# Pyr0-Piezo_Direct_Extruder_Board2_0_1.net
KiCad netlist of a schematic drawn in EAGLE
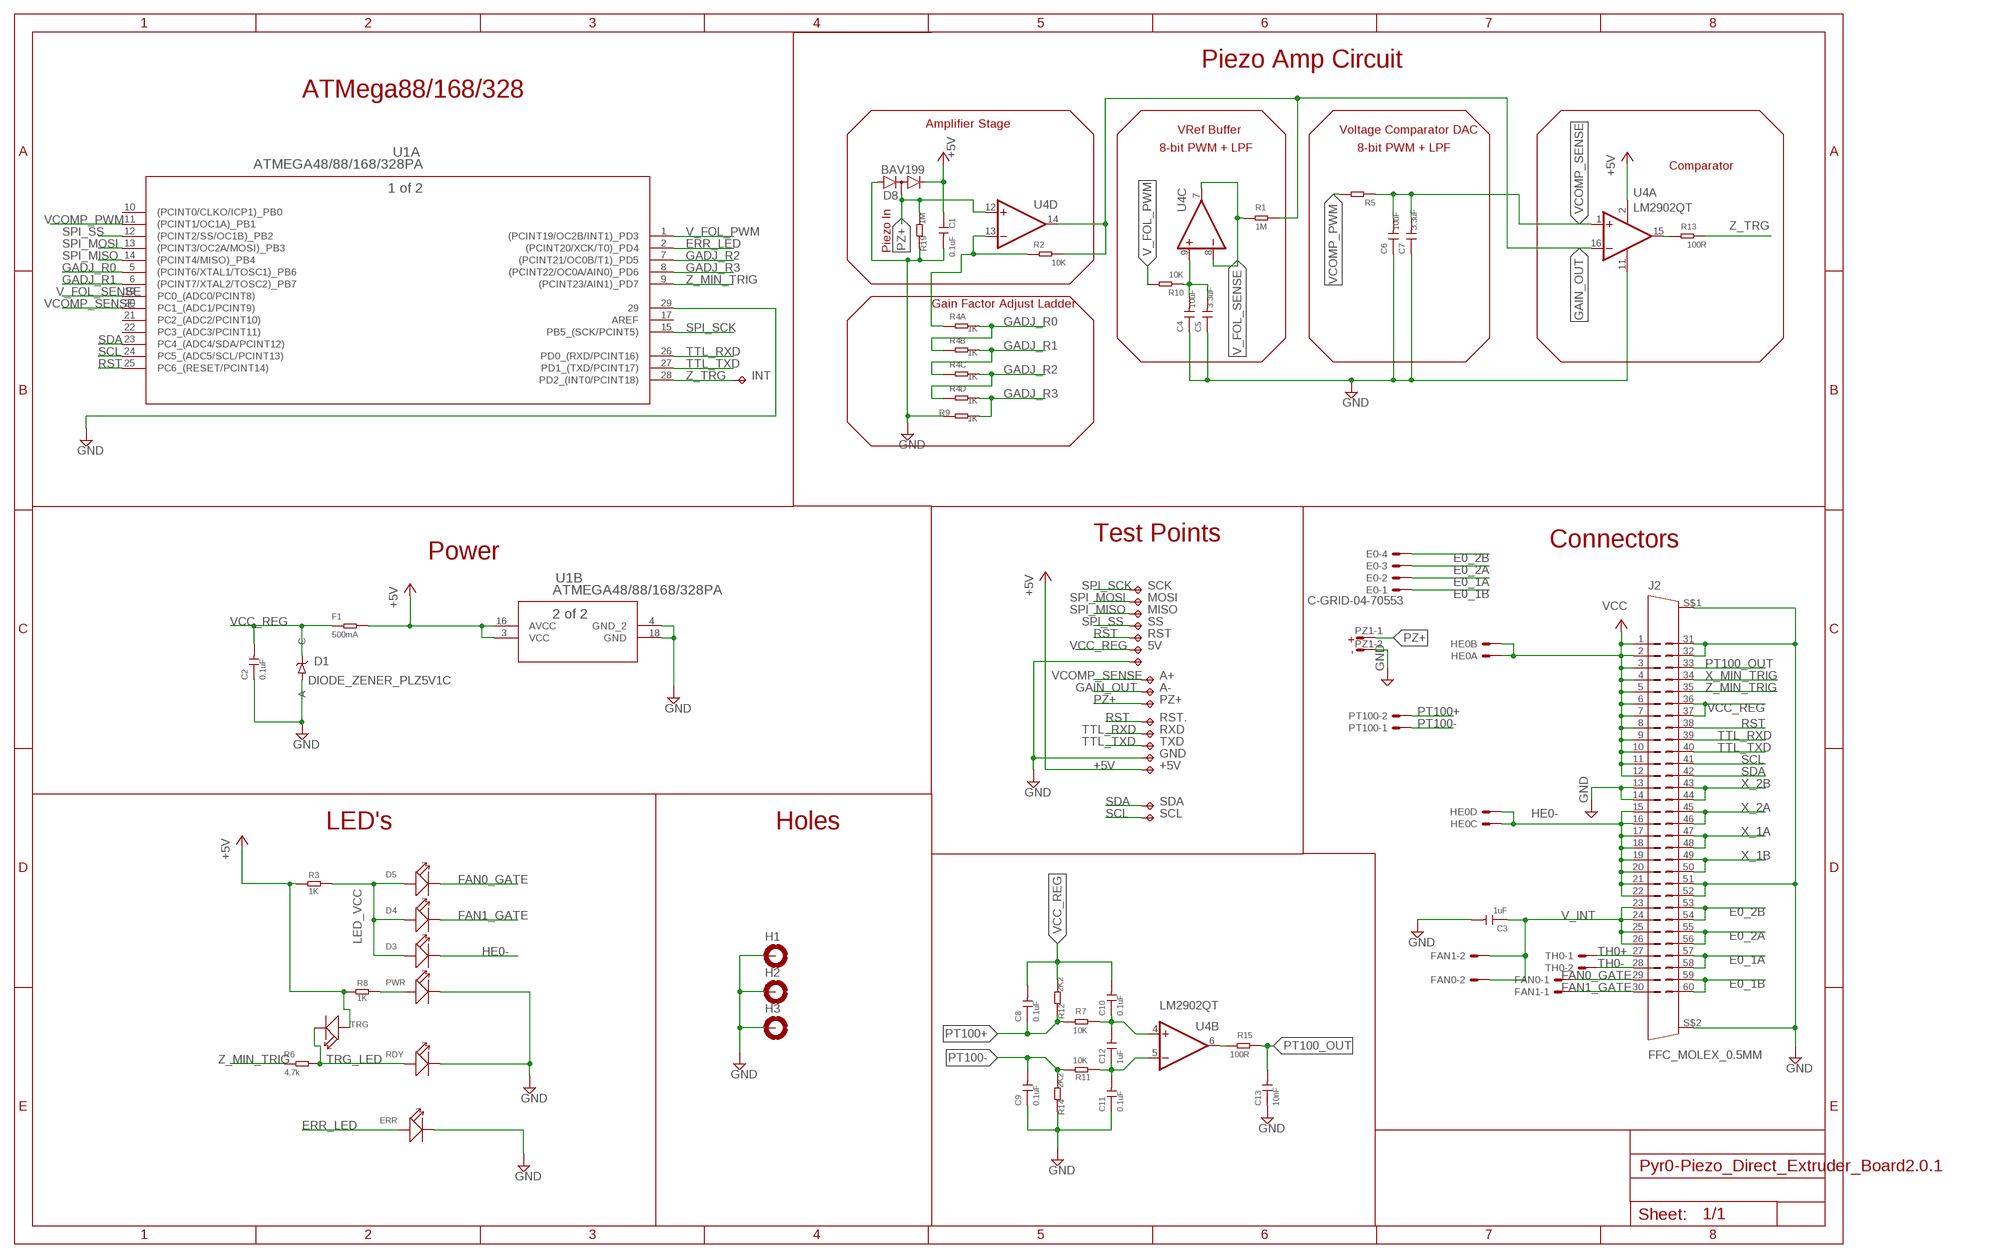
[diagram p0: schematic, sheet 1]

(export (version "E")
  (design (tool "Eeschema 10.0.6"))
  (components
    (comp (ref "+5V")
      (value "TPTP13SQ")
      (footprint "eagle-import:TP13SQ")
      (libsource (lib "eagle-import") (part "testpad_385_TPTP13SQ"))
    )
    (comp (ref "5V")
      (value "TPTP13SQ")
      (footprint "eagle-import:TP13SQ")
      (libsource (lib "eagle-import") (part "TPTP13SQ"))
    )
    (comp (ref "A+")
      (value "TPTP13SQ")
      (footprint "eagle-import:TP13SQ")
      (libsource (lib "eagle-import") (part "TPTP13SQ"))
    )
    (comp (ref "A-")
      (value "TPTP13SQ")
      (footprint "eagle-import:TP13SQ")
      (libsource (lib "eagle-import") (part "TPTP13SQ"))
    )
    (comp (ref "C1")
      (value "0.1uF")
      (footprint "eagle-import:CAPC1005X50")
      (libsource (lib "eagle-import") (part "CERAMIC-1NF-50V-10%-X7R(0402)CAP_0402"))
    )
    (comp (ref "C2")
      (value "0.1uF")
      (footprint "eagle-import:CAPC1005X50")
      (libsource (lib "eagle-import") (part "CERAMIC-1NF-50V-10%-X7R(0402)CAP_0402"))
    )
    (comp (ref "C3")
      (value "1uF")
      (footprint "eagle-import:CAPC1609X80")
      (libsource (lib "eagle-import") (part "SEEED-CAPACITOR_CERAMIC-10UF-25V-10%-X5R(0805)CAP_0603_GEN"))
    )
    (comp (ref "C4")
      (value "10uF")
      (footprint "eagle-import:CAPC1005X50")
      (libsource (lib "eagle-import") (part "CERAMIC-1NF-50V-10%-X7R(0402)CAP_0402"))
    )
    (comp (ref "C5")
      (value "3.3uF")
      (footprint "eagle-import:CAPC1609X80")
      (libsource (lib "eagle-import") (part "SEEED-CAPACITOR_CERAMIC-10UF-25V-10%-X5R(0805)CAP_0603_GEN"))
    )
    (comp (ref "C6")
      (value "10uF")
      (footprint "eagle-import:CAPC1005X50")
      (libsource (lib "eagle-import") (part "CERAMIC-1NF-50V-10%-X7R(0402)CAP_0402"))
    )
    (comp (ref "C7")
      (value "3.3uF")
      (footprint "eagle-import:CAPC1609X80")
      (libsource (lib "eagle-import") (part "SEEED-CAPACITOR_CERAMIC-10UF-25V-10%-X5R(0805)CAP_0603_GEN"))
    )
    (comp (ref "C8")
      (value "0.1uF")
      (footprint "eagle-import:CAPC1005X50")
      (libsource (lib "eagle-import") (part "CERAMIC-1NF-50V-10%-X7R(0402)CAP_0402"))
    )
    (comp (ref "C9")
      (value "0.1uF")
      (footprint "eagle-import:CAPC1005X50")
      (libsource (lib "eagle-import") (part "CERAMIC-1NF-50V-10%-X7R(0402)CAP_0402"))
    )
    (comp (ref "C10")
      (value "0.1uF")
      (footprint "eagle-import:CAPC1005X50")
      (libsource (lib "eagle-import") (part "CERAMIC-1NF-50V-10%-X7R(0402)CAP_0402"))
    )
    (comp (ref "C11")
      (value "0.1uF")
      (footprint "eagle-import:CAPC1005X50")
      (libsource (lib "eagle-import") (part "CERAMIC-1NF-50V-10%-X7R(0402)CAP_0402"))
    )
    (comp (ref "C12")
      (value "1uF")
      (footprint "eagle-import:CAPC1005X50")
      (libsource (lib "eagle-import") (part "CERAMIC-1NF-50V-10%-X7R(0402)CAP_0402"))
    )
    (comp (ref "C13")
      (value "10nF")
      (footprint "eagle-import:CAPC1005X50")
      (libsource (lib "eagle-import") (part "CERAMIC-1NF-50V-10%-X7R(0402)CAP_0402"))
    )
    (comp (ref "D1")
      (value "DIODE_ZENER_PLZ5V1C")
      (footprint "eagle-import:DO-219AC")
      (libsource (lib "eagle-import") (part "DIODE_ZENER_PLZ5V1C"))
    )
    (comp (ref "D3")
      (value "SEEED-LED_SMD-LED-CLEAR-BLUE(0603)LED_0603")
      (footprint "eagle-import:SEEED-LED_LED-0603")
      (libsource (lib "eagle-import") (part "SEEED-LED_SMD-LED-CLEAR-BLUE(0603)LED_0603"))
    )
    (comp (ref "D4")
      (value "SEEED-LED_SMD-LED-CLEAR-BLUE(0603)LED_0603")
      (footprint "eagle-import:SEEED-LED_LED-0603")
      (libsource (lib "eagle-import") (part "SEEED-LED_SMD-LED-CLEAR-BLUE(0603)LED_0603"))
    )
    (comp (ref "D5")
      (value "SEEED-LED_SMD-LED-CLEAR-BLUE(0603)LED_0603")
      (footprint "eagle-import:SEEED-LED_LED-0603")
      (libsource (lib "eagle-import") (part "SEEED-LED_SMD-LED-CLEAR-BLUE(0603)LED_0603"))
    )
    (comp (ref "D8")
      (value "BAV199")
      (footprint "eagle-import:SOT23")
      (libsource (lib "eagle-import") (part "BAV199"))
    )
    (comp (ref "E0")
      (value "C-GRID-04-70553")
      (footprint "eagle-import:70553-04")
      (fields (field (name "MF") "MOLEX"))
      (libsource (lib "eagle-import") (part "C-GRID-04-70553"))
    )
    (comp (ref "ERR")
      (value "SEEED-LED_SMD-LED-CLEAR-BLUE(0603)LED_0603")
      (footprint "eagle-import:SEEED-LED_LED-0603")
      (libsource (lib "eagle-import") (part "SEEED-LED_SMD-LED-CLEAR-BLUE(0603)LED_0603"))
    )
    (comp (ref "F1")
      (value "500mA")
      (footprint "eagle-import:SEEED-RESISTOR_R0603")
      (libsource (lib "eagle-import") (part "SEEED-RESISTOR_SMD-RES-1.5K-1%-1/10W(0603)DETAILED_MODEL"))
    )
    (comp (ref "FAN0")
      (value "CON-MOLEX-2P-1.27MM048")
      (footprint "eagle-import:53048-02")
      (fields (field (name "MF") "MOLEX") (field (name "MPN") "53048-0210"))
      (libsource (lib "eagle-import") (part "CON-MOLEX-2P-1.27MM048"))
    )
    (comp (ref "FAN1")
      (value "CON-MOLEX-2P-1.27MM048")
      (footprint "eagle-import:53048-02")
      (fields (field (name "MF") "MOLEX") (field (name "MPN") "53048-0210"))
      (libsource (lib "eagle-import") (part "CON-MOLEX-2P-1.27MM048"))
    )
    (comp (ref "GND")
      (value "TPTP13SQ")
      (footprint "eagle-import:TP13SQ")
      (libsource (lib "eagle-import") (part "testpad_385_TPTP13SQ"))
    )
    (comp (ref "H1")
      (value "HOLES_MOUNT-PAD-ROUND3.2")
      (footprint "eagle-import:HOLES_3,2-PAD")
      (libsource (lib "eagle-import") (part "HOLES_MOUNT-PAD-ROUND3.2"))
    )
    (comp (ref "H2")
      (value "HOLES_MOUNT-PAD-ROUND3.2")
      (footprint "eagle-import:HOLES_3,2-PAD")
      (libsource (lib "eagle-import") (part "HOLES_MOUNT-PAD-ROUND3.2"))
    )
    (comp (ref "H3")
      (value "HOLES_MOUNT-PAD-ROUND3.2")
      (footprint "eagle-import:HOLES_3,2-PAD")
      (libsource (lib "eagle-import") (part "HOLES_MOUNT-PAD-ROUND3.2"))
    )
    (comp (ref "HE0")
      (value "JST-2.54-2X2JST-DUPONT-2.54-2X2")
      (footprint "eagle-import:HDRRAR4W64P254_2X2_556X736X556B")
      (libsource (lib "eagle-import") (part "JST-2.54-2X2JST-DUPONT-2.54-2X2"))
    )
    (comp (ref "INT")
      (value "TPTP06R")
      (footprint "eagle-import:TP06R")
      (libsource (lib "eagle-import") (part "testpad_385_TPTP06R"))
    )
    (comp (ref "J2")
      (value "FFC_MOLEX_0.5MM")
      (footprint "eagle-import:FFC-60P_0.5_MOLEX_505110-6091")
      (libsource (lib "eagle-import") (part "FFC_MOLEX_0.5MM"))
    )
    (comp (ref "MISO")
      (value "TPTP13SQ")
      (footprint "eagle-import:TP13SQ")
      (libsource (lib "eagle-import") (part "TPTP13SQ"))
    )
    (comp (ref "MOSI")
      (value "TPTP13SQ")
      (footprint "eagle-import:TP13SQ")
      (libsource (lib "eagle-import") (part "TPTP13SQ"))
    )
    (comp (ref "PT100")
      (value "CON-MOLEX-2P-1.27MM048")
      (footprint "eagle-import:53048-02")
      (fields (field (name "MF") "MOLEX") (field (name "MPN") "53048-0210"))
      (libsource (lib "eagle-import") (part "CON-MOLEX-2P-1.27MM048"))
    )
    (comp (ref "PWR")
      (value "SEEED-LED_SMD-LED-CLEAR-BLUE(0603)LED_0603")
      (footprint "eagle-import:SEEED-LED_LED-0603")
      (libsource (lib "eagle-import") (part "SEEED-LED_SMD-LED-CLEAR-BLUE(0603)LED_0603"))
    )
    (comp (ref "PZ+")
      (value "TPTP13SQ")
      (footprint "eagle-import:TP13SQ")
      (libsource (lib "eagle-import") (part "TPTP13SQ"))
    )
    (comp (ref "PZ1")
      (value "CON-MOLEX-2P-1.27MM048")
      (footprint "eagle-import:53048-02")
      (fields (field (name "MF") "MOLEX") (field (name "MPN") "53048-0210"))
      (libsource (lib "eagle-import") (part "CON-MOLEX-2P-1.27MM048"))
    )
    (comp (ref "R1")
      (value "1M")
      (footprint "eagle-import:R0402")
      (fields (field (name "MPN") "RC0402JR-070RL"))
      (libsource (lib "eagle-import") (part "SMD-RES-0R-5%-1/16W(0402)"))
    )
    (comp (ref "R2")
      (value "10K")
      (footprint "eagle-import:R0402")
      (fields (field (name "MPN") "RC0402JR-070RL"))
      (libsource (lib "eagle-import") (part "SMD-RES-0R-5%-1/16W(0402)"))
    )
    (comp (ref "R3")
      (value "1K")
      (footprint "eagle-import:R0402")
      (fields (field (name "MPN") "RC0402JR-070RL"))
      (libsource (lib "eagle-import") (part "SMD-RES-0R-5%-1/16W(0402)"))
    )
    (comp (ref "R4")
      (value "1K")
      (footprint "eagle-import:EXBN8V")
      (libsource (lib "eagle-import") (part "RESISTOR_NETWORK_X40804"))
    )
    (comp (ref "R5")
      (value "10K")
      (footprint "eagle-import:SEEED-RESISTOR_R0603")
      (libsource (lib "eagle-import") (part "SEEED-RESISTOR_SMD-RES-1.5K-1%-1/10W(0603)DETAILED_MODEL"))
    )
    (comp (ref "R6")
      (value "4.7k")
      (footprint "eagle-import:R0402")
      (fields (field (name "MPN") "RC0402JR-070RL"))
      (libsource (lib "eagle-import") (part "SMD-RES-0R-5%-1/16W(0402)"))
    )
    (comp (ref "R7")
      (value "10K")
      (footprint "eagle-import:R0402")
      (fields (field (name "MPN") "RC0402JR-070RL"))
      (libsource (lib "eagle-import") (part "SMD-RES-0R-5%-1/16W(0402)"))
    )
    (comp (ref "R8")
      (value "1K")
      (footprint "eagle-import:R0402")
      (fields (field (name "MPN") "RC0402JR-070RL"))
      (libsource (lib "eagle-import") (part "SMD-RES-0R-5%-1/16W(0402)"))
    )
    (comp (ref "R9")
      (value "1K")
      (footprint "eagle-import:R0402")
      (fields (field (name "MPN") "RC0402JR-070RL"))
      (libsource (lib "eagle-import") (part "SMD-RES-0R-5%-1/16W(0402)"))
    )
    (comp (ref "R10")
      (value "10K")
      (footprint "eagle-import:R0402")
      (fields (field (name "MPN") "RC0402JR-070RL"))
      (libsource (lib "eagle-import") (part "SMD-RES-0R-5%-1/16W(0402)"))
    )
    (comp (ref "R11")
      (value "10K")
      (footprint "eagle-import:R0402")
      (fields (field (name "MPN") "RC0402JR-070RL"))
      (libsource (lib "eagle-import") (part "SMD-RES-0R-5%-1/16W(0402)"))
    )
    (comp (ref "R12")
      (value "2K2")
      (footprint "eagle-import:R0402")
      (fields (field (name "MPN") "RC0402JR-070RL"))
      (libsource (lib "eagle-import") (part "SMD-RES-0R-5%-1/16W(0402)"))
    )
    (comp (ref "R13")
      (value "100R")
      (footprint "eagle-import:R0402")
      (fields (field (name "MPN") "RC0402JR-070RL"))
      (libsource (lib "eagle-import") (part "SMD-RES-0R-5%-1/16W(0402)"))
    )
    (comp (ref "R14")
      (value "2K2")
      (footprint "eagle-import:R0402")
      (fields (field (name "MPN") "RC0402JR-070RL"))
      (libsource (lib "eagle-import") (part "SMD-RES-0R-5%-1/16W(0402)"))
    )
    (comp (ref "R15")
      (value "100R")
      (footprint "eagle-import:R0402")
      (fields (field (name "MPN") "RC0402JR-070RL"))
      (libsource (lib "eagle-import") (part "SMD-RES-0R-5%-1/16W(0402)"))
    )
    (comp (ref "R19")
      (value "1M")
      (footprint "eagle-import:R0402")
      (fields (field (name "MPN") "RC0402JR-070RL"))
      (libsource (lib "eagle-import") (part "SMD-RES-0R-5%-1/16W(0402)"))
    )
    (comp (ref "RDY")
      (value "SEEED-LED_SMD-LED-CLEAR-BLUE(0603)LED_0603")
      (footprint "eagle-import:SEEED-LED_LED-0603")
      (libsource (lib "eagle-import") (part "SEEED-LED_SMD-LED-CLEAR-BLUE(0603)LED_0603"))
    )
    (comp (ref "RST")
      (value "TPTP13SQ")
      (footprint "eagle-import:TP13SQ")
      (libsource (lib "eagle-import") (part "TPTP13SQ"))
    )
    (comp (ref "RST.")
      (value "TPTP13SQ")
      (footprint "eagle-import:TP13SQ")
      (libsource (lib "eagle-import") (part "testpad_385_TPTP13SQ"))
    )
    (comp (ref "RXD")
      (value "TPTP13SQ")
      (footprint "eagle-import:TP13SQ")
      (libsource (lib "eagle-import") (part "testpad_385_TPTP13SQ"))
    )
    (comp (ref "SCK")
      (value "TPTP13SQ")
      (footprint "eagle-import:TP13SQ")
      (libsource (lib "eagle-import") (part "TPTP13SQ"))
    )
    (comp (ref "SCL")
      (value "TPTP13SQ")
      (footprint "eagle-import:TP13SQ")
      (libsource (lib "eagle-import") (part "testpad_385_TPTP13SQ"))
    )
    (comp (ref "SDA")
      (value "TPTP13SQ")
      (footprint "eagle-import:TP13SQ")
      (libsource (lib "eagle-import") (part "testpad_385_TPTP13SQ"))
    )
    (comp (ref "SS")
      (value "TPTP06R")
      (footprint "eagle-import:TP06R")
      (libsource (lib "eagle-import") (part "testpad_385_TPTP06R"))
    )
    (comp (ref "TH0")
      (value "CON-MOLEX-2P-1.27MM048")
      (footprint "eagle-import:53048-02")
      (fields (field (name "MF") "MOLEX") (field (name "MPN") "53048-0210"))
      (libsource (lib "eagle-import") (part "CON-MOLEX-2P-1.27MM048"))
    )
    (comp (ref "TRG")
      (value "SEEED-LED_SMD-LED-CLEAR-BLUE(0603)LED_0603")
      (footprint "eagle-import:SEEED-LED_LED-0603")
      (libsource (lib "eagle-import") (part "SEEED-LED_SMD-LED-CLEAR-BLUE(0603)LED_0603"))
    )
    (comp (ref "TXD")
      (value "TPTP13SQ")
      (footprint "eagle-import:TP13SQ")
      (libsource (lib "eagle-import") (part "testpad_385_TPTP13SQ"))
    )
    (comp (ref "U1")
      (value "ATMEGA48/88/168/328PA")
      (footprint "eagle-import:28M1")
      (fields (field (name "MANUFACTURER_PART_NUMBER") "ATMEGA48PAMMHR"))
      (libsource (lib "eagle-import") (part "ATMEGA48/88/168/328PA"))
    )
    (comp (ref "U4")
      (value "LM2902QT")
      (footprint "eagle-import:QFN16")
      (libsource (lib "eagle-import") (part "LM2902QT"))
    )
    (comp (ref "⏚")
      (value "TPTP13SQ")
      (footprint "eagle-import:TP13SQ")
      (libsource (lib "eagle-import") (part "testpad_385_TPTP13SQ"))
    )
  )
  (nets
    (net (code "1") (name "+5V") (class "Default")
      (node (ref "+5V") (pin "TP") (pinfunction "TP_TP") (pintype "input"))
      (node (ref "C1") (pin "1") (pinfunction "1_1") (pintype "passive"))
      (node (ref "D8") (pin "2") (pinfunction "C_2") (pintype "passive"))
      (node (ref "F1") (pin "2") (pinfunction "2_2") (pintype "passive"))
      (node (ref "R3") (pin "1") (pinfunction "1_1") (pintype "passive"))
      (node (ref "R8") (pin "1") (pinfunction "1_1") (pintype "passive"))
      (node (ref "TRG") (pin "+") (pinfunction "+_+") (pintype "passive"))
      (node (ref "U1") (pin "16") (pinfunction "AVCC_16") (pintype "power_in"))
      (node (ref "U1") (pin "3") (pinfunction "VCC_3") (pintype "power_in"))
      (node (ref "U4") (pin "2") (pinfunction "V+_2") (pintype "power_in"))
    )
    (net (code "2") (name "/E0_1A") (class "Default")
      (node (ref "E0") (pin "2") (pinfunction "S_2") (pintype "passive"))
      (node (ref "J2") (pin "57") (pinfunction "63_57") (pintype "passive"))
      (node (ref "J2") (pin "58") (pinfunction "64_58") (pintype "passive"))
    )
    (net (code "3") (name "/E0_1B") (class "Default")
      (node (ref "E0") (pin "1") (pinfunction "S_1") (pintype "passive"))
      (node (ref "J2") (pin "59") (pinfunction "65_59") (pintype "passive"))
      (node (ref "J2") (pin "60") (pinfunction "66_60") (pintype "passive"))
    )
    (net (code "4") (name "/E0_2A") (class "Default")
      (node (ref "E0") (pin "3") (pinfunction "S_3") (pintype "passive"))
      (node (ref "J2") (pin "55") (pinfunction "61_55") (pintype "passive"))
      (node (ref "J2") (pin "56") (pinfunction "62_56") (pintype "passive"))
    )
    (net (code "5") (name "/E0_2B") (class "Default")
      (node (ref "E0") (pin "4") (pinfunction "S_4") (pintype "passive"))
      (node (ref "J2") (pin "53") (pinfunction "59_53") (pintype "passive"))
      (node (ref "J2") (pin "54") (pinfunction "60_54") (pintype "passive"))
    )
    (net (code "6") (name "/ERR_LED") (class "Default")
      (node (ref "ERR") (pin "+") (pinfunction "+_+") (pintype "passive"))
      (node (ref "U1") (pin "2") (pinfunction "(PCINT20/XCK/T0)_PD4_2") (pintype "bidirectional"))
    )
    (net (code "7") (name "/FAN0_GATE") (class "Default")
      (node (ref "D5") (pin "-") (pinfunction "-_-") (pintype "passive"))
      (node (ref "FAN0") (pin "1") (pinfunction "S_1") (pintype "passive"))
      (node (ref "J2") (pin "29") (pinfunction "31_29") (pintype "passive"))
    )
    (net (code "8") (name "/FAN1_GATE") (class "Default")
      (node (ref "D4") (pin "-") (pinfunction "-_-") (pintype "passive"))
      (node (ref "FAN1") (pin "1") (pinfunction "S_1") (pintype "passive"))
      (node (ref "J2") (pin "30") (pinfunction "32_30") (pintype "passive"))
    )
    (net (code "9") (name "/GADJ_R0") (class "Default")
      (node (ref "R4") (pin "2") (pinfunction "1_2") (pintype "passive"))
      (node (ref "R4") (pin "8") (pinfunction "2_8") (pintype "passive"))
      (node (ref "U1") (pin "5") (pinfunction "(PCINT6/XTAL1/TOSC1)_PB6_5") (pintype "bidirectional"))
    )
    (net (code "10") (name "/GADJ_R1") (class "Default")
      (node (ref "R4") (pin "3") (pinfunction "1_3") (pintype "passive"))
      (node (ref "R4") (pin "7") (pinfunction "2_7") (pintype "passive"))
      (node (ref "U1") (pin "6") (pinfunction "(PCINT7/XTAL2/TOSC2)_PB7_6") (pintype "bidirectional"))
    )
    (net (code "11") (name "/GADJ_R2") (class "Default")
      (node (ref "R4") (pin "4") (pinfunction "1_4") (pintype "passive"))
      (node (ref "R4") (pin "6") (pinfunction "2_6") (pintype "passive"))
      (node (ref "U1") (pin "7") (pinfunction "(PCINT21/OC0B/T1)_PD5_7") (pintype "bidirectional"))
    )
    (net (code "12") (name "/GADJ_R3") (class "Default")
      (node (ref "R4") (pin "5") (pinfunction "2_5") (pintype "passive"))
      (node (ref "R9") (pin "2") (pinfunction "2_2") (pintype "passive"))
      (node (ref "U1") (pin "8") (pinfunction "(PCINT22/OC0A/AIN0)_PD6_8") (pintype "bidirectional"))
    )
    (net (code "13") (name "/HE0-") (class "Default")
      (node (ref "D3") (pin "-") (pinfunction "-_-") (pintype "passive"))
      (node (ref "HE0") (pin "3") (pinfunction "S_3") (pintype "passive"))
      (node (ref "HE0") (pin "4") (pinfunction "S_4") (pintype "passive"))
      (node (ref "J2") (pin "15") (pinfunction "17_15") (pintype "passive"))
      (node (ref "J2") (pin "16") (pinfunction "18_16") (pintype "passive"))
      (node (ref "J2") (pin "17") (pinfunction "19_17") (pintype "passive"))
      (node (ref "J2") (pin "18") (pinfunction "20_18") (pintype "passive"))
      (node (ref "J2") (pin "19") (pinfunction "21_19") (pintype "passive"))
      (node (ref "J2") (pin "20") (pinfunction "22_20") (pintype "passive"))
      (node (ref "J2") (pin "21") (pinfunction "23_21") (pintype "passive"))
      (node (ref "J2") (pin "22") (pinfunction "24_22") (pintype "passive"))
    )
    (net (code "14") (name "/LED_VCC") (class "Default")
      (node (ref "D3") (pin "+") (pinfunction "+_+") (pintype "passive"))
      (node (ref "D4") (pin "+") (pinfunction "+_+") (pintype "passive"))
      (node (ref "D5") (pin "+") (pinfunction "+_+") (pintype "passive"))
      (node (ref "R3") (pin "2") (pinfunction "2_2") (pintype "passive"))
    )
    (net (code "15") (name "/RST") (class "Default")
      (node (ref "J2") (pin "38") (pinfunction "44_38") (pintype "passive"))
      (node (ref "RST") (pin "TP") (pinfunction "TP_TP") (pintype "input"))
      (node (ref "RST.") (pin "TP") (pinfunction "TP_TP") (pintype "input"))
      (node (ref "U1") (pin "25") (pinfunction "PC6_(RESET/PCINT14)_25") (pintype "bidirectional"))
    )
    (net (code "16") (name "/SCL") (class "Default")
      (node (ref "J2") (pin "41") (pinfunction "47_41") (pintype "passive"))
      (node (ref "SCL") (pin "TP") (pinfunction "TP_TP") (pintype "input"))
      (node (ref "U1") (pin "24") (pinfunction "PC5_(ADC5/SCL/PCINT13)_24") (pintype "bidirectional"))
    )
    (net (code "17") (name "/SDA") (class "Default")
      (node (ref "J2") (pin "42") (pinfunction "48_42") (pintype "passive"))
      (node (ref "SDA") (pin "TP") (pinfunction "TP_TP") (pintype "input"))
      (node (ref "U1") (pin "23") (pinfunction "PC4_(ADC4/SDA/PCINT12)_23") (pintype "bidirectional"))
    )
    (net (code "18") (name "/SPI_MISO") (class "Default")
      (node (ref "MISO") (pin "TP") (pinfunction "TP_TP") (pintype "input"))
      (node (ref "U1") (pin "14") (pinfunction "(PCINT4/MISO)_PB4_14") (pintype "bidirectional"))
    )
    (net (code "19") (name "/SPI_MOSI") (class "Default")
      (node (ref "MOSI") (pin "TP") (pinfunction "TP_TP") (pintype "input"))
      (node (ref "U1") (pin "13") (pinfunction "(PCINT3/OC2A/MOSI)_PB3_13") (pintype "bidirectional"))
    )
    (net (code "20") (name "/SPI_SCK") (class "Default")
      (node (ref "SCK") (pin "TP") (pinfunction "TP_TP") (pintype "input"))
      (node (ref "U1") (pin "15") (pinfunction "PB5_(SCK/PCINT5)_15") (pintype "bidirectional"))
    )
    (net (code "21") (name "/SPI_SS") (class "Default")
      (node (ref "SS") (pin "TP") (pinfunction "TP_TP") (pintype "input"))
      (node (ref "U1") (pin "12") (pinfunction "(PCINT2/SS/OC1B)_PB2_12") (pintype "bidirectional"))
    )
    (net (code "22") (name "/TH0+") (class "Default")
      (node (ref "J2") (pin "27") (pinfunction "29_27") (pintype "passive"))
      (node (ref "TH0") (pin "1") (pinfunction "S_1") (pintype "passive"))
    )
    (net (code "23") (name "/TH0-") (class "Default")
      (node (ref "J2") (pin "28") (pinfunction "30_28") (pintype "passive"))
      (node (ref "TH0") (pin "2") (pinfunction "S_2") (pintype "passive"))
    )
    (net (code "24") (name "/TRG_LED") (class "Default")
      (node (ref "R6") (pin "2") (pinfunction "2_2") (pintype "passive"))
      (node (ref "RDY") (pin "+") (pinfunction "+_+") (pintype "passive"))
      (node (ref "TRG") (pin "-") (pinfunction "-_-") (pintype "passive"))
    )
    (net (code "25") (name "/TTL_RXD") (class "Default")
      (node (ref "J2") (pin "39") (pinfunction "45_39") (pintype "passive"))
      (node (ref "RXD") (pin "TP") (pinfunction "TP_TP") (pintype "input"))
      (node (ref "U1") (pin "26") (pinfunction "PD0_(RXD/PCINT16)_26") (pintype "bidirectional"))
    )
    (net (code "26") (name "/TTL_TXD") (class "Default")
      (node (ref "J2") (pin "40") (pinfunction "46_40") (pintype "passive"))
      (node (ref "TXD") (pin "TP") (pinfunction "TP_TP") (pintype "input"))
      (node (ref "U1") (pin "27") (pinfunction "PD1_(TXD/PCINT17)_27") (pintype "bidirectional"))
    )
    (net (code "27") (name "/V_INT") (class "Default")
      (node (ref "C3") (pin "1") (pinfunction "1_1") (pintype "passive"))
      (node (ref "FAN0") (pin "2") (pinfunction "S_2") (pintype "passive"))
      (node (ref "FAN1") (pin "2") (pinfunction "S_2") (pintype "passive"))
      (node (ref "J2") (pin "23") (pinfunction "25_23") (pintype "passive"))
      (node (ref "J2") (pin "24") (pinfunction "26_24") (pintype "passive"))
      (node (ref "J2") (pin "25") (pinfunction "27_25") (pintype "passive"))
      (node (ref "J2") (pin "26") (pinfunction "28_26") (pintype "passive"))
    )
    (net (code "28") (name "/X_1A") (class "Default")
      (node (ref "J2") (pin "47") (pinfunction "53_47") (pintype "passive"))
      (node (ref "J2") (pin "48") (pinfunction "54_48") (pintype "passive"))
    )
    (net (code "29") (name "/X_1B") (class "Default")
      (node (ref "J2") (pin "49") (pinfunction "55_49") (pintype "passive"))
      (node (ref "J2") (pin "50") (pinfunction "56_50") (pintype "passive"))
    )
    (net (code "30") (name "/X_2A") (class "Default")
      (node (ref "J2") (pin "45") (pinfunction "51_45") (pintype "passive"))
      (node (ref "J2") (pin "46") (pinfunction "52_46") (pintype "passive"))
    )
    (net (code "31") (name "/X_2B") (class "Default")
      (node (ref "J2") (pin "43") (pinfunction "49_43") (pintype "passive"))
      (node (ref "J2") (pin "44") (pinfunction "50_44") (pintype "passive"))
    )
    (net (code "32") (name "/X_MIN_TRIG") (class "Default")
      (node (ref "J2") (pin "34") (pinfunction "40_34") (pintype "passive"))
    )
    (net (code "33") (name "/Z_MIN_TRIG") (class "Default")
      (node (ref "J2") (pin "35") (pinfunction "41_35") (pintype "passive"))
      (node (ref "R6") (pin "1") (pinfunction "1_1") (pintype "passive"))
      (node (ref "U1") (pin "9") (pinfunction "(PCINT23/AIN1)_PD7_9") (pintype "bidirectional"))
    )
    (net (code "34") (name "/Z_TRG") (class "Default")
      (node (ref "INT") (pin "TP") (pinfunction "TP_TP") (pintype "input"))
      (node (ref "R13") (pin "2") (pinfunction "2_2") (pintype "passive"))
      (node (ref "U1") (pin "28") (pinfunction "PD2_(INT0/PCINT18)_28") (pintype "bidirectional"))
    )
    (net (code "35") (name "GAIN_OUT") (class "Default")
      (node (ref "A-") (pin "TP") (pinfunction "TP_TP") (pintype "input"))
      (node (ref "R1") (pin "2") (pinfunction "2_2") (pintype "passive"))
      (node (ref "R2") (pin "2") (pinfunction "2_2") (pintype "passive"))
      (node (ref "U4") (pin "14") (pinfunction "OUT_14") (pintype "output"))
      (node (ref "U4") (pin "16") (pinfunction "-IN_16") (pintype "input"))
    )
    (net (code "36") (name "GND") (class "Default")
      (node (ref "C1") (pin "2") (pinfunction "2_2") (pintype "passive"))
      (node (ref "C11") (pin "1") (pinfunction "1_1") (pintype "passive"))
      (node (ref "C13") (pin "1") (pinfunction "1_1") (pintype "passive"))
      (node (ref "C2") (pin "1") (pinfunction "1_1") (pintype "passive"))
      (node (ref "C3") (pin "2") (pinfunction "2_2") (pintype "passive"))
      (node (ref "C4") (pin "1") (pinfunction "1_1") (pintype "passive"))
      (node (ref "C5") (pin "1") (pinfunction "1_1") (pintype "passive"))
      (node (ref "C6") (pin "1") (pinfunction "1_1") (pintype "passive"))
      (node (ref "C7") (pin "1") (pinfunction "1_1") (pintype "passive"))
      (node (ref "C9") (pin "1") (pinfunction "1_1") (pintype "passive"))
      (node (ref "D1") (pin "P$1") (pinfunction "A_P$1") (pintype "passive"))
      (node (ref "D8") (pin "1") (pinfunction "A_1") (pintype "passive"))
      (node (ref "ERR") (pin "-") (pinfunction "-_-") (pintype "passive"))
      (node (ref "GND") (pin "TP") (pinfunction "TP_TP") (pintype "input"))
      (node (ref "H1") (pin "B3,2") (pinfunction "MOUNT_B3,2") (pintype "passive"))
      (node (ref "H2") (pin "B3,2") (pinfunction "MOUNT_B3,2") (pintype "passive"))
      (node (ref "H3") (pin "B3,2") (pinfunction "MOUNT_B3,2") (pintype "passive"))
      (node (ref "J2") (pin "13") (pinfunction "15_13") (pintype "passive"))
      (node (ref "J2") (pin "14") (pinfunction "16_14") (pintype "passive"))
      (node (ref "J2") (pin "31") (pinfunction "37_31") (pintype "passive"))
      (node (ref "J2") (pin "32") (pinfunction "38_32") (pintype "passive"))
      (node (ref "J2") (pin "51") (pinfunction "57_51") (pintype "passive"))
      (node (ref "J2") (pin "52") (pinfunction "58_52") (pintype "passive"))
      (node (ref "J2") (pin "S$1") (pinfunction "S_S$1") (pintype "passive"))
      (node (ref "J2") (pin "S$2") (pinfunction "S_S$2") (pintype "passive"))
      (node (ref "PWR") (pin "-") (pinfunction "-_-") (pintype "passive"))
      (node (ref "PZ1") (pin "2") (pinfunction "S_2") (pintype "passive"))
      (node (ref "R14") (pin "1") (pinfunction "1_1") (pintype "passive"))
      (node (ref "R19") (pin "1") (pinfunction "1_1") (pintype "passive"))
      (node (ref "R9") (pin "1") (pinfunction "1_1") (pintype "passive"))
      (node (ref "RDY") (pin "-") (pinfunction "-_-") (pintype "passive"))
      (node (ref "U1") (pin "18") (pinfunction "GND_18") (pintype "power_in"))
      (node (ref "U1") (pin "29") (pinfunction "29_29") (pintype "passive"))
      (node (ref "U1") (pin "4") (pinfunction "GND_2_4") (pintype "power_in"))
      (node (ref "U4") (pin "11") (pinfunction "V-_11") (pintype "power_in"))
      (node (ref "⏚") (pin "TP") (pinfunction "TP_TP") (pintype "input"))
    )
    (net (code "37") (name "Net-(PWR-Pad+)") (class "Default")
      (node (ref "PWR") (pin "+") (pinfunction "+_+") (pintype "passive"))
      (node (ref "R8") (pin "2") (pinfunction "2_2") (pintype "passive"))
    )
    (net (code "38") (name "Net-(U4A-OUT)") (class "Default")
      (node (ref "R13") (pin "1") (pinfunction "1_1") (pintype "passive"))
      (node (ref "U4") (pin "15") (pinfunction "OUT_15") (pintype "output"))
    )
    (net (code "39") (name "Net-(U4B-+IN)") (class "Default")
      (node (ref "C10") (pin "1") (pinfunction "1_1") (pintype "passive"))
      (node (ref "C12") (pin "2") (pinfunction "2_2") (pintype "passive"))
      (node (ref "R7") (pin "1") (pinfunction "1_1") (pintype "passive"))
      (node (ref "U4") (pin "4") (pinfunction "+IN_4") (pintype "input"))
    )
    (net (code "40") (name "Net-(U4B--IN)") (class "Default")
      (node (ref "C11") (pin "2") (pinfunction "2_2") (pintype "passive"))
      (node (ref "C12") (pin "1") (pinfunction "1_1") (pintype "passive"))
      (node (ref "R11") (pin "1") (pinfunction "1_1") (pintype "passive"))
      (node (ref "U4") (pin "5") (pinfunction "-IN_5") (pintype "input"))
    )
    (net (code "41") (name "Net-(U4B-OUT)") (class "Default")
      (node (ref "R15") (pin "2") (pinfunction "2_2") (pintype "passive"))
      (node (ref "U4") (pin "6") (pinfunction "OUT_6") (pintype "output"))
    )
    (net (code "42") (name "Net-(U4C-+IN)") (class "Default")
      (node (ref "C4") (pin "2") (pinfunction "2_2") (pintype "passive"))
      (node (ref "C5") (pin "2") (pinfunction "2_2") (pintype "passive"))
      (node (ref "R10") (pin "1") (pinfunction "1_1") (pintype "passive"))
      (node (ref "U4") (pin "9") (pinfunction "+IN_9") (pintype "input"))
    )
    (net (code "43") (name "Net-(U4D--IN)") (class "Default")
      (node (ref "R2") (pin "1") (pinfunction "1_1") (pintype "passive"))
      (node (ref "R4") (pin "1") (pinfunction "1_1") (pintype "passive"))
      (node (ref "U4") (pin "13") (pinfunction "-IN_13") (pintype "input"))
    )
    (net (code "44") (name "PT100+") (class "Default")
      (node (ref "C8") (pin "1") (pinfunction "1_1") (pintype "passive"))
      (node (ref "PT100") (pin "2") (pinfunction "S_2") (pintype "passive"))
      (node (ref "R12") (pin "1") (pinfunction "1_1") (pintype "passive"))
      (node (ref "R7") (pin "2") (pinfunction "2_2") (pintype "passive"))
    )
    (net (code "45") (name "PT100-") (class "Default")
      (node (ref "C9") (pin "2") (pinfunction "2_2") (pintype "passive"))
      (node (ref "PT100") (pin "1") (pinfunction "S_1") (pintype "passive"))
      (node (ref "R11") (pin "2") (pinfunction "2_2") (pintype "passive"))
      (node (ref "R14") (pin "2") (pinfunction "2_2") (pintype "passive"))
    )
    (net (code "46") (name "PT100_OUT") (class "Default")
      (node (ref "C13") (pin "2") (pinfunction "2_2") (pintype "passive"))
      (node (ref "J2") (pin "33") (pinfunction "39_33") (pintype "passive"))
      (node (ref "R15") (pin "1") (pinfunction "1_1") (pintype "passive"))
    )
    (net (code "47") (name "PZ+") (class "Default")
      (node (ref "D8") (pin "3") (pinfunction "AC_3") (pintype "passive"))
      (node (ref "PZ+") (pin "TP") (pinfunction "TP_TP") (pintype "input"))
      (node (ref "PZ1") (pin "1") (pinfunction "S_1") (pintype "passive"))
      (node (ref "R19") (pin "2") (pinfunction "2_2") (pintype "passive"))
      (node (ref "U4") (pin "12") (pinfunction "+IN_12") (pintype "input"))
    )
    (net (code "48") (name "VCC") (class "Default")
      (node (ref "HE0") (pin "1") (pinfunction "S_1") (pintype "passive"))
      (node (ref "HE0") (pin "2") (pinfunction "S_2") (pintype "passive"))
      (node (ref "J2") (pin "1") (pinfunction "3_1") (pintype "passive"))
      (node (ref "J2") (pin "10") (pinfunction "12_10") (pintype "passive"))
      (node (ref "J2") (pin "11") (pinfunction "13_11") (pintype "passive"))
      (node (ref "J2") (pin "12") (pinfunction "14_12") (pintype "passive"))
      (node (ref "J2") (pin "2") (pinfunction "4_2") (pintype "passive"))
      (node (ref "J2") (pin "3") (pinfunction "5_3") (pintype "passive"))
      (node (ref "J2") (pin "4") (pinfunction "6_4") (pintype "passive"))
      (node (ref "J2") (pin "5") (pinfunction "7_5") (pintype "passive"))
      (node (ref "J2") (pin "6") (pinfunction "8_6") (pintype "passive"))
      (node (ref "J2") (pin "7") (pinfunction "9_7") (pintype "passive"))
      (node (ref "J2") (pin "8") (pinfunction "10_8") (pintype "passive"))
      (node (ref "J2") (pin "9") (pinfunction "11_9") (pintype "passive"))
    )
    (net (code "49") (name "VCC_REG") (class "Default")
      (node (ref "5V") (pin "TP") (pinfunction "TP_TP") (pintype "input"))
      (node (ref "C10") (pin "2") (pinfunction "2_2") (pintype "passive"))
      (node (ref "C2") (pin "2") (pinfunction "2_2") (pintype "passive"))
      (node (ref "C8") (pin "2") (pinfunction "2_2") (pintype "passive"))
      (node (ref "D1") (pin "P$2") (pinfunction "C_P$2") (pintype "passive"))
      (node (ref "F1") (pin "1") (pinfunction "1_1") (pintype "passive"))
      (node (ref "J2") (pin "36") (pinfunction "42_36") (pintype "passive"))
      (node (ref "J2") (pin "37") (pinfunction "43_37") (pintype "passive"))
      (node (ref "R12") (pin "2") (pinfunction "2_2") (pintype "passive"))
    )
    (net (code "50") (name "VCOMP_PWM") (class "Default")
      (node (ref "R5") (pin "2") (pinfunction "2_2") (pintype "passive"))
      (node (ref "U1") (pin "11") (pinfunction "(PCINT1/OC1A)_PB1_11") (pintype "bidirectional"))
    )
    (net (code "51") (name "VCOMP_SENSE") (class "Default")
      (node (ref "A+") (pin "TP") (pinfunction "TP_TP") (pintype "input"))
      (node (ref "C6") (pin "2") (pinfunction "2_2") (pintype "passive"))
      (node (ref "C7") (pin "2") (pinfunction "2_2") (pintype "passive"))
      (node (ref "R5") (pin "1") (pinfunction "1_1") (pintype "passive"))
      (node (ref "U1") (pin "20") (pinfunction "PC1_(ADC1/PCINT9)_20") (pintype "bidirectional"))
      (node (ref "U4") (pin "1") (pinfunction "+IN_1") (pintype "input"))
    )
    (net (code "52") (name "V_FOL_PWM") (class "Default")
      (node (ref "R10") (pin "2") (pinfunction "2_2") (pintype "passive"))
      (node (ref "U1") (pin "1") (pinfunction "(PCINT19/OC2B/INT1)_PD3_1") (pintype "bidirectional"))
    )
    (net (code "53") (name "V_FOL_SENSE") (class "Default")
      (node (ref "R1") (pin "1") (pinfunction "1_1") (pintype "passive"))
      (node (ref "U1") (pin "19") (pinfunction "PC0_(ADC0/PCINT8)_19") (pintype "bidirectional"))
      (node (ref "U4") (pin "7") (pinfunction "OUT_7") (pintype "output"))
      (node (ref "U4") (pin "8") (pinfunction "-IN_8") (pintype "input"))
    )
    (net (code "54") (name "unconnected-(U1A-(PCINT0{slash}CLKO{slash}ICP1)_PB0-Pad10)") (class "Default")
      (node (ref "U1") (pin "10") (pinfunction "(PCINT0/CLKO/ICP1)_PB0_10") (pintype "bidirectional"))
    )
    (net (code "55") (name "unconnected-(U1A-AREF-Pad17)") (class "Default")
      (node (ref "U1") (pin "17") (pinfunction "AREF_17") (pintype "passive"))
    )
    (net (code "56") (name "unconnected-(U1A-PC2_(ADC2{slash}PCINT10)-Pad21)") (class "Default")
      (node (ref "U1") (pin "21") (pinfunction "PC2_(ADC2/PCINT10)_21") (pintype "bidirectional"))
    )
    (net (code "57") (name "unconnected-(U1A-PC3_(ADC3{slash}PCINT11)-Pad22)") (class "Default")
      (node (ref "U1") (pin "22") (pinfunction "PC3_(ADC3/PCINT11)_22") (pintype "bidirectional"))
    )
  )
)
